# Meishino_v11.net
KiCad netlist of a schematic drawn in EAGLE
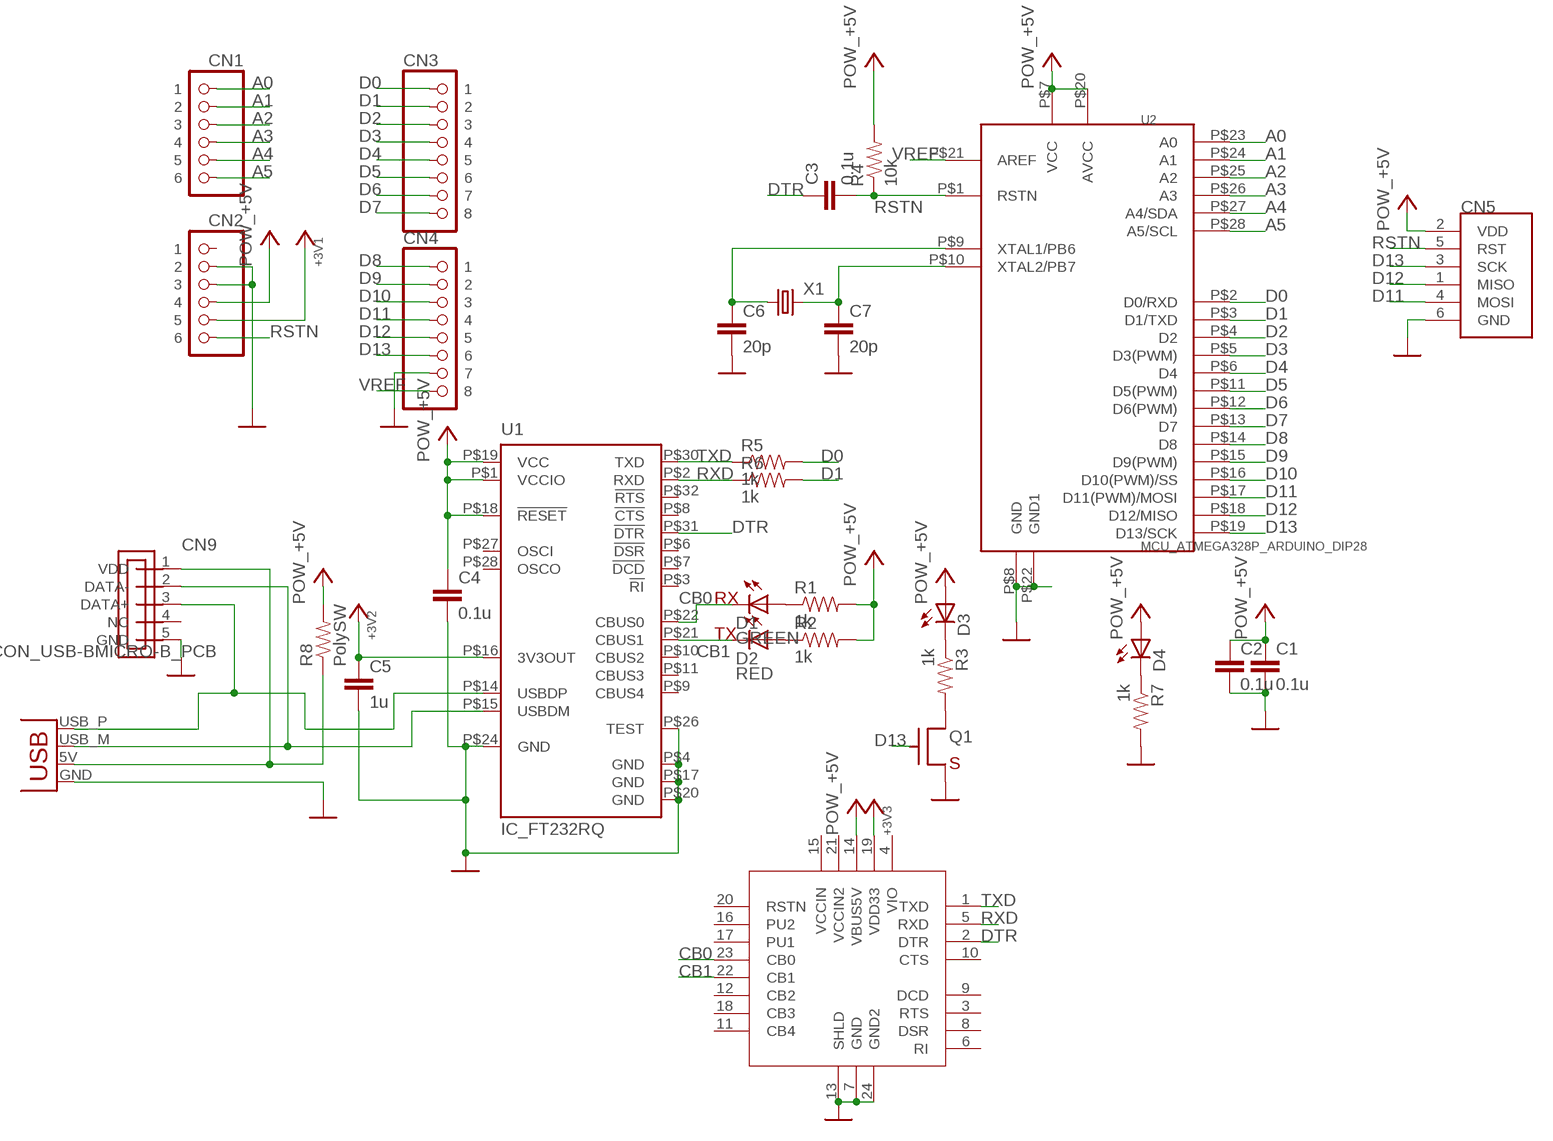
[diagram p0: schematic, sheet 1]

(export (version "E")
  (design (tool "Eeschema 10.0.6"))
  (components
    (comp (ref "C1")
      (value "0.1u")
      (footprint "eagle-import:CAP_TH_5MM_L")
      (libsource (lib "eagle-import") (part "CAPTH_5MML"))
    )
    (comp (ref "C2")
      (value "0.1u")
      (footprint "eagle-import:CAP_TH_5MM_L")
      (libsource (lib "eagle-import") (part "CAPTH_5MML"))
    )
    (comp (ref "C3")
      (value "0.1u")
      (footprint "eagle-import:CAP_TH_5MM_L")
      (libsource (lib "eagle-import") (part "CAPTH_5MML"))
    )
    (comp (ref "C4")
      (value "0.1u")
      (footprint "eagle-import:CAP_TH_5MM_L")
      (libsource (lib "eagle-import") (part "CAPTH_5MML"))
    )
    (comp (ref "C5")
      (value "1u")
      (footprint "eagle-import:CAP_TH_5MM_L")
      (libsource (lib "eagle-import") (part "CAPTH_5MML"))
    )
    (comp (ref "C6")
      (value "20p")
      (footprint "eagle-import:CAP_TH_5MM_L")
      (libsource (lib "eagle-import") (part "CAPTH_5MML"))
    )
    (comp (ref "C7")
      (value "20p")
      (footprint "eagle-import:CAP_TH_5MM_L")
      (libsource (lib "eagle-import") (part "CAPTH_5MML"))
    )
    (comp (ref "CN1")
      (value "CON_PINHD-1X6")
      (footprint "eagle-import:1X06")
      (libsource (lib "eagle-import") (part "CON_PINHD-1X6"))
    )
    (comp (ref "CN2")
      (value "CON_PINHD-1X6")
      (footprint "eagle-import:1X06")
      (libsource (lib "eagle-import") (part "CON_PINHD-1X6"))
    )
    (comp (ref "CN3")
      (value "CON_PINHD-1X8")
      (footprint "eagle-import:1X08")
      (libsource (lib "eagle-import") (part "CON_PINHD-1X8"))
    )
    (comp (ref "CN4")
      (value "CON_PINHD-1X8")
      (footprint "eagle-import:1X08")
      (libsource (lib "eagle-import") (part "CON_PINHD-1X8"))
    )
    (comp (ref "CN5")
      (value "CON_AVRISPTH")
      (footprint "eagle-import:2X03R")
      (libsource (lib "eagle-import") (part "CON_AVRISPTH"))
    )
    (comp (ref "CN9")
      (value "CON_USB-BMICRO-B_PCB")
      (footprint "eagle-import:USB-MICRO-PCB")
      (libsource (lib "eagle-import") (part "CON_USB-BMICRO-B_PCB"))
    )
    (comp (ref "D1")
      (value "GREEN")
      (footprint "eagle-import:SPARKFUN_LED5MM")
      (libsource (lib "eagle-import") (part "LED5MM"))
    )
    (comp (ref "D2")
      (value "RED")
      (footprint "eagle-import:SPARKFUN_LED5MM")
      (libsource (lib "eagle-import") (part "LED5MM"))
    )
    (comp (ref "D3")
      (value "LED5MM")
      (footprint "eagle-import:SPARKFUN_LED5MM")
      (libsource (lib "eagle-import") (part "LED5MM"))
    )
    (comp (ref "D4")
      (value "LED5MM")
      (footprint "eagle-import:SPARKFUN_LED5MM")
      (libsource (lib "eagle-import") (part "LED5MM"))
    )
    (comp (ref "JP2")
      (value "CON_USBPCB")
      (footprint "eagle-import:USB-A-PCB")
      (libsource (lib "eagle-import") (part "CON_USBPCB"))
    )
    (comp (ref "Q1")
      (value "TR_NMOS_2N7000")
      (footprint "eagle-import:TO-92")
      (libsource (lib "eagle-import") (part "TR_NMOS_2N7000"))
    )
    (comp (ref "R1")
      (value "1k")
      (footprint "eagle-import:R_TH_10MM_L")
      (libsource (lib "eagle-import") (part "RESTH_10MML"))
    )
    (comp (ref "R2")
      (value "1k")
      (footprint "eagle-import:R_TH_10MM_L")
      (libsource (lib "eagle-import") (part "RESTH_10MML"))
    )
    (comp (ref "R3")
      (value "1k")
      (footprint "eagle-import:R_TH_10MM_L")
      (libsource (lib "eagle-import") (part "RESTH_10MML"))
    )
    (comp (ref "R4")
      (value "10k")
      (footprint "eagle-import:R_TH_10MM_L")
      (libsource (lib "eagle-import") (part "RESTH_10MML"))
    )
    (comp (ref "R5")
      (value "1k")
      (footprint "eagle-import:R_TH_10MM_L")
      (libsource (lib "eagle-import") (part "RESTH_10MML"))
    )
    (comp (ref "R6")
      (value "1k")
      (footprint "eagle-import:R_TH_10MM_L")
      (libsource (lib "eagle-import") (part "RESTH_10MML"))
    )
    (comp (ref "R7")
      (value "1k")
      (footprint "eagle-import:R_TH_10MM_L")
      (libsource (lib "eagle-import") (part "RESTH_10MML"))
    )
    (comp (ref "R8")
      (value "PolySW")
      (footprint "eagle-import:R_TH_10MM_L")
      (libsource (lib "eagle-import") (part "RESTH_10MML"))
    )
    (comp (ref "U1")
      (value "IC_FT232RQ")
      (footprint "eagle-import:QFN32")
      (libsource (lib "eagle-import") (part "IC_FT232RQ"))
    )
    (comp (ref "U2")
      (value "MCU_ATMEGA328P_ARDUINO_DIP28")
      (footprint "eagle-import:DIP-28P(300MIL)")
      (libsource (lib "eagle-import") (part "MCU_ATMEGA328P_ARDUINO_DIP28"))
    )
    (comp (ref "U3")
      (value "MOD_AE_FT232_DIP24")
      (footprint "eagle-import:DIP24_600MIL")
      (libsource (lib "eagle-import") (part "MOD_AE_FT232_DIP24"))
    )
    (comp (ref "X1")
      (value "XTAL2HC49US")
      (footprint "eagle-import:HC49US")
      (libsource (lib "eagle-import") (part "XTAL2HC49US"))
    )
  )
  (nets
    (net (code "1") (name "/A0") (class "Default")
      (node (ref "CN1") (pin "1") (pinfunction "1_1") (pintype "passive"))
      (node (ref "U2") (pin "P$23") (pinfunction "A0_P$23") (pintype "bidirectional"))
    )
    (net (code "2") (name "/A1") (class "Default")
      (node (ref "CN1") (pin "2") (pinfunction "2_2") (pintype "passive"))
      (node (ref "U2") (pin "P$24") (pinfunction "A1_P$24") (pintype "bidirectional"))
    )
    (net (code "3") (name "/A2") (class "Default")
      (node (ref "CN1") (pin "3") (pinfunction "3_3") (pintype "passive"))
      (node (ref "U2") (pin "P$25") (pinfunction "A2_P$25") (pintype "bidirectional"))
    )
    (net (code "4") (name "/A3") (class "Default")
      (node (ref "CN1") (pin "4") (pinfunction "4_4") (pintype "passive"))
      (node (ref "U2") (pin "P$26") (pinfunction "A3_P$26") (pintype "bidirectional"))
    )
    (net (code "5") (name "/A4") (class "Default")
      (node (ref "CN1") (pin "5") (pinfunction "5_5") (pintype "passive"))
      (node (ref "U2") (pin "P$27") (pinfunction "A4/SDA_P$27") (pintype "bidirectional"))
    )
    (net (code "6") (name "/A5") (class "Default")
      (node (ref "CN1") (pin "6") (pinfunction "6_6") (pintype "passive"))
      (node (ref "U2") (pin "P$28") (pinfunction "A5/SCL_P$28") (pintype "bidirectional"))
    )
    (net (code "7") (name "/CB0") (class "Default")
      (node (ref "D1") (pin "K") (pinfunction "C_K") (pintype "passive"))
      (node (ref "U1") (pin "P$22") (pinfunction "CBUS0_P$22") (pintype "bidirectional"))
      (node (ref "U3") (pin "23") (pinfunction "CB0_23") (pintype "bidirectional"))
    )
    (net (code "8") (name "/CB1") (class "Default")
      (node (ref "D2") (pin "K") (pinfunction "C_K") (pintype "passive"))
      (node (ref "U1") (pin "P$21") (pinfunction "CBUS1_P$21") (pintype "bidirectional"))
      (node (ref "U3") (pin "22") (pinfunction "CB1_22") (pintype "bidirectional"))
    )
    (net (code "9") (name "/D0") (class "Default")
      (node (ref "CN3") (pin "1") (pinfunction "1_1") (pintype "passive"))
      (node (ref "R5") (pin "2") (pinfunction "2_2") (pintype "passive"))
      (node (ref "U2") (pin "P$2") (pinfunction "D0/RXD_P$2") (pintype "bidirectional"))
    )
    (net (code "10") (name "/D1") (class "Default")
      (node (ref "CN3") (pin "2") (pinfunction "2_2") (pintype "passive"))
      (node (ref "R6") (pin "2") (pinfunction "2_2") (pintype "passive"))
      (node (ref "U2") (pin "P$3") (pinfunction "D1/TXD_P$3") (pintype "bidirectional"))
    )
    (net (code "11") (name "/D2") (class "Default")
      (node (ref "CN3") (pin "3") (pinfunction "3_3") (pintype "passive"))
      (node (ref "U2") (pin "P$4") (pinfunction "D2_P$4") (pintype "bidirectional"))
    )
    (net (code "12") (name "/D3") (class "Default")
      (node (ref "CN3") (pin "4") (pinfunction "4_4") (pintype "passive"))
      (node (ref "U2") (pin "P$5") (pinfunction "D3(PWM)_P$5") (pintype "bidirectional"))
    )
    (net (code "13") (name "/D4") (class "Default")
      (node (ref "CN3") (pin "5") (pinfunction "5_5") (pintype "passive"))
      (node (ref "U2") (pin "P$6") (pinfunction "D4_P$6") (pintype "bidirectional"))
    )
    (net (code "14") (name "/D5") (class "Default")
      (node (ref "CN3") (pin "6") (pinfunction "6_6") (pintype "passive"))
      (node (ref "U2") (pin "P$11") (pinfunction "D5(PWM)_P$11") (pintype "bidirectional"))
    )
    (net (code "15") (name "/D6") (class "Default")
      (node (ref "CN3") (pin "7") (pinfunction "7_7") (pintype "passive"))
      (node (ref "U2") (pin "P$12") (pinfunction "D6(PWM)_P$12") (pintype "bidirectional"))
    )
    (net (code "16") (name "/D7") (class "Default")
      (node (ref "CN3") (pin "8") (pinfunction "8_8") (pintype "passive"))
      (node (ref "U2") (pin "P$13") (pinfunction "D7_P$13") (pintype "bidirectional"))
    )
    (net (code "17") (name "/D8") (class "Default")
      (node (ref "CN4") (pin "1") (pinfunction "1_1") (pintype "passive"))
      (node (ref "U2") (pin "P$14") (pinfunction "D8_P$14") (pintype "bidirectional"))
    )
    (net (code "18") (name "/D9") (class "Default")
      (node (ref "CN4") (pin "2") (pinfunction "2_2") (pintype "passive"))
      (node (ref "U2") (pin "P$15") (pinfunction "D9(PWM)_P$15") (pintype "bidirectional"))
    )
    (net (code "19") (name "/D10") (class "Default")
      (node (ref "CN4") (pin "3") (pinfunction "3_3") (pintype "passive"))
      (node (ref "U2") (pin "P$16") (pinfunction "D10(PWM)/SS_P$16") (pintype "bidirectional"))
    )
    (net (code "20") (name "/D11") (class "Default")
      (node (ref "CN4") (pin "4") (pinfunction "4_4") (pintype "passive"))
      (node (ref "CN5") (pin "4") (pinfunction "MOSI_4") (pintype "bidirectional"))
      (node (ref "U2") (pin "P$17") (pinfunction "D11(PWM)/MOSI_P$17") (pintype "bidirectional"))
    )
    (net (code "21") (name "/D12") (class "Default")
      (node (ref "CN4") (pin "5") (pinfunction "5_5") (pintype "passive"))
      (node (ref "CN5") (pin "1") (pinfunction "MISO_1") (pintype "bidirectional"))
      (node (ref "U2") (pin "P$18") (pinfunction "D12/MISO_P$18") (pintype "bidirectional"))
    )
    (net (code "22") (name "/D13") (class "Default")
      (node (ref "CN4") (pin "6") (pinfunction "6_6") (pintype "passive"))
      (node (ref "CN5") (pin "3") (pinfunction "SCK_3") (pintype "bidirectional"))
      (node (ref "Q1") (pin "2") (pinfunction "G_2") (pintype "bidirectional"))
      (node (ref "U2") (pin "P$19") (pinfunction "D13/SCK_P$19") (pintype "bidirectional"))
    )
    (net (code "23") (name "/DTR") (class "Default")
      (node (ref "C3") (pin "1") (pinfunction "1_1") (pintype "passive"))
      (node (ref "U1") (pin "P$31") (pinfunction "~{DTR}_P$31") (pintype "output"))
      (node (ref "U3") (pin "2") (pinfunction "DTR_2") (pintype "bidirectional"))
    )
    (net (code "24") (name "/RSTN") (class "Default")
      (node (ref "C3") (pin "2") (pinfunction "2_2") (pintype "passive"))
      (node (ref "CN2") (pin "6") (pinfunction "6_6") (pintype "passive"))
      (node (ref "CN5") (pin "5") (pinfunction "RST_5") (pintype "bidirectional"))
      (node (ref "R4") (pin "1") (pinfunction "1_1") (pintype "passive"))
      (node (ref "U2") (pin "P$1") (pinfunction "RSTN_P$1") (pintype "bidirectional"))
    )
    (net (code "25") (name "/RXD") (class "Default")
      (node (ref "R6") (pin "1") (pinfunction "1_1") (pintype "passive"))
      (node (ref "U1") (pin "P$2") (pinfunction "RXD_P$2") (pintype "input"))
      (node (ref "U3") (pin "5") (pinfunction "RXD_5") (pintype "bidirectional"))
    )
    (net (code "26") (name "/TXD") (class "Default")
      (node (ref "R5") (pin "1") (pinfunction "1_1") (pintype "passive"))
      (node (ref "U1") (pin "P$30") (pinfunction "TXD_P$30") (pintype "output"))
      (node (ref "U3") (pin "1") (pinfunction "TXD_1") (pintype "bidirectional"))
    )
    (net (code "27") (name "/VREF") (class "Default")
      (node (ref "CN4") (pin "8") (pinfunction "8_8") (pintype "passive"))
      (node (ref "U2") (pin "P$21") (pinfunction "AREF_P$21") (pintype "bidirectional"))
    )
    (net (code "28") (name "Net-(CN9-DATA+)") (class "Default")
      (node (ref "CN9") (pin "3") (pinfunction "DATA+_3") (pintype "bidirectional"))
      (node (ref "JP2") (pin "USB_P") (pinfunction "D+_USB_P") (pintype "bidirectional"))
      (node (ref "U1") (pin "P$14") (pinfunction "USBDP_P$14") (pintype "bidirectional"))
    )
    (net (code "29") (name "Net-(CN9-DATA-)") (class "Default")
      (node (ref "CN9") (pin "2") (pinfunction "DATA-_2") (pintype "bidirectional"))
      (node (ref "JP2") (pin "USB_M") (pinfunction "D-_USB_M") (pintype "bidirectional"))
      (node (ref "U1") (pin "P$15") (pinfunction "USBDM_P$15") (pintype "bidirectional"))
    )
    (net (code "30") (name "Net-(CN9-VDD)") (class "Default")
      (node (ref "CN9") (pin "1") (pinfunction "VDD_1") (pintype "power_in"))
      (node (ref "JP2") (pin "5V") (pinfunction "VBUS_5V") (pintype "bidirectional"))
      (node (ref "R8") (pin "1") (pinfunction "1_1") (pintype "passive"))
    )
    (net (code "31") (name "Net-(D1-PadA)") (class "Default")
      (node (ref "D1") (pin "A") (pinfunction "A_A") (pintype "passive"))
      (node (ref "R1") (pin "1") (pinfunction "1_1") (pintype "passive"))
    )
    (net (code "32") (name "Net-(D2-PadA)") (class "Default")
      (node (ref "D2") (pin "A") (pinfunction "A_A") (pintype "passive"))
      (node (ref "R2") (pin "1") (pinfunction "1_1") (pintype "passive"))
    )
    (net (code "33") (name "Net-(D3-C)") (class "Default")
      (node (ref "D3") (pin "K") (pinfunction "C_K") (pintype "passive"))
      (node (ref "R3") (pin "1") (pinfunction "1_1") (pintype "passive"))
    )
    (net (code "34") (name "Net-(D4-C)") (class "Default")
      (node (ref "D4") (pin "K") (pinfunction "C_K") (pintype "passive"))
      (node (ref "R7") (pin "1") (pinfunction "1_1") (pintype "passive"))
    )
    (net (code "35") (name "Net-(Q1-D)") (class "Default")
      (node (ref "Q1") (pin "3") (pinfunction "D_3") (pintype "bidirectional"))
      (node (ref "R3") (pin "2") (pinfunction "2_2") (pintype "passive"))
    )
    (net (code "36") (name "Net-(U2-XTAL1{slash}PB6)") (class "Default")
      (node (ref "C6") (pin "1") (pinfunction "1_1") (pintype "passive"))
      (node (ref "U2") (pin "P$9") (pinfunction "XTAL1/PB6_P$9") (pintype "bidirectional"))
      (node (ref "X1") (pin "1") (pinfunction "1_1") (pintype "passive"))
    )
    (net (code "37") (name "Net-(U2-XTAL2{slash}PB7)") (class "Default")
      (node (ref "C7") (pin "1") (pinfunction "1_1") (pintype "passive"))
      (node (ref "U2") (pin "P$10") (pinfunction "XTAL2/PB7_P$10") (pintype "bidirectional"))
      (node (ref "X1") (pin "2") (pinfunction "2_2") (pintype "passive"))
    )
    (net (code "38") (name "POW_+3V3") (class "Default")
      (node (ref "C5") (pin "1") (pinfunction "1_1") (pintype "passive"))
      (node (ref "CN2") (pin "5") (pinfunction "5_5") (pintype "passive"))
      (node (ref "U1") (pin "P$16") (pinfunction "3V3OUT_P$16") (pintype "output"))
      (node (ref "U3") (pin "19") (pinfunction "VDD33_19") (pintype "bidirectional"))
    )
    (net (code "39") (name "POW_+5V") (class "Default")
      (node (ref "C1") (pin "1") (pinfunction "1_1") (pintype "passive"))
      (node (ref "C2") (pin "1") (pinfunction "1_1") (pintype "passive"))
      (node (ref "C4") (pin "1") (pinfunction "1_1") (pintype "passive"))
      (node (ref "CN2") (pin "4") (pinfunction "4_4") (pintype "passive"))
      (node (ref "CN5") (pin "2") (pinfunction "VDD_2") (pintype "bidirectional"))
      (node (ref "D3") (pin "A") (pinfunction "A_A") (pintype "passive"))
      (node (ref "D4") (pin "A") (pinfunction "A_A") (pintype "passive"))
      (node (ref "R1") (pin "2") (pinfunction "2_2") (pintype "passive"))
      (node (ref "R2") (pin "2") (pinfunction "2_2") (pintype "passive"))
      (node (ref "R4") (pin "2") (pinfunction "2_2") (pintype "passive"))
      (node (ref "R8") (pin "2") (pinfunction "2_2") (pintype "passive"))
      (node (ref "U1") (pin "P$1") (pinfunction "VCCIO_P$1") (pintype "power_in"))
      (node (ref "U1") (pin "P$18") (pinfunction "~{RESET}_P$18") (pintype "input"))
      (node (ref "U1") (pin "P$19") (pinfunction "VCC_P$19") (pintype "power_in"))
      (node (ref "U2") (pin "P$20") (pinfunction "AVCC_P$20") (pintype "power_in"))
      (node (ref "U2") (pin "P$7") (pinfunction "VCC_P$7") (pintype "power_in"))
      (node (ref "U3") (pin "14") (pinfunction "VBUS5V_14") (pintype "bidirectional"))
    )
    (net (code "40") (name "POW_GND") (class "Default")
      (node (ref "C1") (pin "2") (pinfunction "2_2") (pintype "passive"))
      (node (ref "C2") (pin "2") (pinfunction "2_2") (pintype "passive"))
      (node (ref "C4") (pin "2") (pinfunction "2_2") (pintype "passive"))
      (node (ref "C5") (pin "2") (pinfunction "2_2") (pintype "passive"))
      (node (ref "C6") (pin "2") (pinfunction "2_2") (pintype "passive"))
      (node (ref "C7") (pin "2") (pinfunction "2_2") (pintype "passive"))
      (node (ref "CN2") (pin "2") (pinfunction "2_2") (pintype "passive"))
      (node (ref "CN2") (pin "3") (pinfunction "3_3") (pintype "passive"))
      (node (ref "CN4") (pin "7") (pinfunction "7_7") (pintype "passive"))
      (node (ref "CN5") (pin "6") (pinfunction "GND_6") (pintype "bidirectional"))
      (node (ref "CN9") (pin "5") (pinfunction "GND_5") (pintype "power_in"))
      (node (ref "JP2") (pin "GND") (pinfunction "GND_GND") (pintype "bidirectional"))
      (node (ref "Q1") (pin "1") (pinfunction "S_1") (pintype "bidirectional"))
      (node (ref "R7") (pin "2") (pinfunction "2_2") (pintype "passive"))
      (node (ref "U1") (pin "P$17") (pinfunction "GND_P$17") (pintype "power_in"))
      (node (ref "U1") (pin "P$20") (pinfunction "GND_P$20") (pintype "power_in"))
      (node (ref "U1") (pin "P$24") (pinfunction "GND_P$24") (pintype "power_in"))
      (node (ref "U1") (pin "P$26") (pinfunction "TEST_P$26") (pintype "input"))
      (node (ref "U1") (pin "P$4") (pinfunction "GND_P$4") (pintype "power_in"))
      (node (ref "U2") (pin "P$22") (pinfunction "GND1_P$22") (pintype "power_in"))
      (node (ref "U2") (pin "P$8") (pinfunction "GND_P$8") (pintype "power_in"))
      (node (ref "U3") (pin "13") (pinfunction "SHLD_13") (pintype "bidirectional"))
      (node (ref "U3") (pin "24") (pinfunction "GND2_24") (pintype "bidirectional"))
      (node (ref "U3") (pin "7") (pinfunction "GND_7") (pintype "bidirectional"))
    )
    (net (code "41") (name "unconnected-(CN2-Pad1)") (class "Default")
      (node (ref "CN2") (pin "1") (pinfunction "1_1") (pintype "passive"))
    )
    (net (code "42") (name "unconnected-(CN9-NC-Pad4)") (class "Default")
      (node (ref "CN9") (pin "4") (pinfunction "NC_4") (pintype "bidirectional"))
    )
    (net (code "43") (name "unconnected-(U1-CBUS2-PadP$10)") (class "Default")
      (node (ref "U1") (pin "P$10") (pinfunction "CBUS2_P$10") (pintype "bidirectional"))
    )
    (net (code "44") (name "unconnected-(U1-CBUS3-PadP$11)") (class "Default")
      (node (ref "U1") (pin "P$11") (pinfunction "CBUS3_P$11") (pintype "bidirectional"))
    )
    (net (code "45") (name "unconnected-(U1-CBUS4-PadP$9)") (class "Default")
      (node (ref "U1") (pin "P$9") (pinfunction "CBUS4_P$9") (pintype "bidirectional"))
    )
    (net (code "46") (name "unconnected-(U1-OSCI-PadP$27)") (class "Default")
      (node (ref "U1") (pin "P$27") (pinfunction "OSCI_P$27") (pintype "input"))
    )
    (net (code "47") (name "unconnected-(U1-OSCO-PadP$28)") (class "Default")
      (node (ref "U1") (pin "P$28") (pinfunction "OSCO_P$28") (pintype "output"))
    )
    (net (code "48") (name "unconnected-(U1-~{CTS}-PadP$8)") (class "Default")
      (node (ref "U1") (pin "P$8") (pinfunction "~{CTS}_P$8") (pintype "input"))
    )
    (net (code "49") (name "unconnected-(U1-~{DCD}-PadP$7)") (class "Default")
      (node (ref "U1") (pin "P$7") (pinfunction "~{DCD}_P$7") (pintype "input"))
    )
    (net (code "50") (name "unconnected-(U1-~{DSR}-PadP$6)") (class "Default")
      (node (ref "U1") (pin "P$6") (pinfunction "~{DSR}_P$6") (pintype "input"))
    )
    (net (code "51") (name "unconnected-(U1-~{RI}-PadP$3)") (class "Default")
      (node (ref "U1") (pin "P$3") (pinfunction "~{RI}_P$3") (pintype "input"))
    )
    (net (code "52") (name "unconnected-(U1-~{RTS}-PadP$32)") (class "Default")
      (node (ref "U1") (pin "P$32") (pinfunction "~{RTS}_P$32") (pintype "output"))
    )
    (net (code "53") (name "unconnected-(U3-CB2-Pad12)") (class "Default")
      (node (ref "U3") (pin "12") (pinfunction "CB2_12") (pintype "bidirectional"))
    )
    (net (code "54") (name "unconnected-(U3-CB3-Pad18)") (class "Default")
      (node (ref "U3") (pin "18") (pinfunction "CB3_18") (pintype "bidirectional"))
    )
    (net (code "55") (name "unconnected-(U3-CB4-Pad11)") (class "Default")
      (node (ref "U3") (pin "11") (pinfunction "CB4_11") (pintype "bidirectional"))
    )
    (net (code "56") (name "unconnected-(U3-CTS-Pad10)") (class "Default")
      (node (ref "U3") (pin "10") (pinfunction "CTS_10") (pintype "bidirectional"))
    )
    (net (code "57") (name "unconnected-(U3-DCD-Pad9)") (class "Default")
      (node (ref "U3") (pin "9") (pinfunction "DCD_9") (pintype "bidirectional"))
    )
    (net (code "58") (name "unconnected-(U3-DSR-Pad8)") (class "Default")
      (node (ref "U3") (pin "8") (pinfunction "DSR_8") (pintype "bidirectional"))
    )
    (net (code "59") (name "unconnected-(U3-PU1-Pad17)") (class "Default")
      (node (ref "U3") (pin "17") (pinfunction "PU1_17") (pintype "bidirectional"))
    )
    (net (code "60") (name "unconnected-(U3-PU2-Pad16)") (class "Default")
      (node (ref "U3") (pin "16") (pinfunction "PU2_16") (pintype "bidirectional"))
    )
    (net (code "61") (name "unconnected-(U3-RI-Pad6)") (class "Default")
      (node (ref "U3") (pin "6") (pinfunction "RI_6") (pintype "bidirectional"))
    )
    (net (code "62") (name "unconnected-(U3-RSTN-Pad20)") (class "Default")
      (node (ref "U3") (pin "20") (pinfunction "RSTN_20") (pintype "bidirectional"))
    )
    (net (code "63") (name "unconnected-(U3-RTS-Pad3)") (class "Default")
      (node (ref "U3") (pin "3") (pinfunction "RTS_3") (pintype "bidirectional"))
    )
    (net (code "64") (name "unconnected-(U3-VCCIN-Pad15)") (class "Default")
      (node (ref "U3") (pin "15") (pinfunction "VCCIN_15") (pintype "bidirectional"))
    )
    (net (code "65") (name "unconnected-(U3-VCCIN2-Pad21)") (class "Default")
      (node (ref "U3") (pin "21") (pinfunction "VCCIN2_21") (pintype "bidirectional"))
    )
    (net (code "66") (name "unconnected-(U3-VIO-Pad4)") (class "Default")
      (node (ref "U3") (pin "4") (pinfunction "VIO_4") (pintype "bidirectional"))
    )
  )
)
